# Adapter.net
KiCad netlist of a schematic drawn in Altium Designer
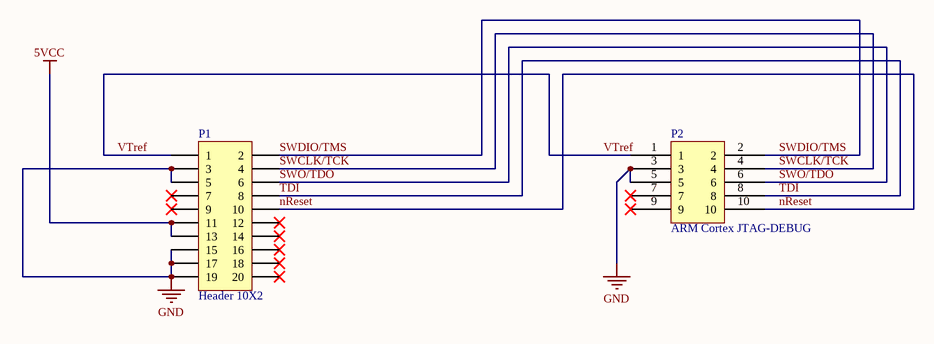
[diagram p0: Adapter.SchDoc]

(export (version "E")
  (design (tool "Eeschema 10.0.6"))
  (components
    (comp (ref "P1")
      (value "Header 10X2")
      (footprint "HDR2X10")
      (description "Header, 10-Pin, Dual row")
      (fields (field (name "PUBLISHER") "Altium Limited"))
      (libsource (lib "Miscellaneous Connectors") (part "Header 10X2"))
    )
    (comp (ref "P2")
      (value "ARM Cortex JTAG-DEBUG")
      (footprint "FTSH-105-XX-X-DV")
      (libsource (lib "Adams Altium Library") (part "ARM Cortex JTAG-DEBUG Header"))
    )
  )
  (nets
    (net (code "1") (name "/SWCLK{slash}TCK") (class "Default")
      (node (ref "P1") (pin "4") (pinfunction "4_4") (pintype "passive"))
      (node (ref "P2") (pin "4") (pinfunction "4_4") (pintype "passive"))
    )
    (net (code "2") (name "/SWDIO{slash}TMS") (class "Default")
      (node (ref "P1") (pin "2") (pinfunction "2_2") (pintype "passive"))
      (node (ref "P2") (pin "2") (pinfunction "2_2") (pintype "passive"))
    )
    (net (code "3") (name "/SWO{slash}TDO") (class "Default")
      (node (ref "P1") (pin "6") (pinfunction "6_6") (pintype "passive"))
      (node (ref "P2") (pin "6") (pinfunction "6_6") (pintype "passive"))
    )
    (net (code "4") (name "/TDI") (class "Default")
      (node (ref "P1") (pin "8") (pinfunction "8_8") (pintype "passive"))
      (node (ref "P2") (pin "8") (pinfunction "8_8") (pintype "passive"))
    )
    (net (code "5") (name "/VTref") (class "Default")
      (node (ref "P1") (pin "1") (pinfunction "1_1") (pintype "passive"))
      (node (ref "P2") (pin "1") (pinfunction "1_1") (pintype "passive"))
    )
    (net (code "6") (name "/nReset") (class "Default")
      (node (ref "P1") (pin "10") (pinfunction "10_10") (pintype "passive"))
      (node (ref "P2") (pin "10") (pinfunction "10_10") (pintype "passive"))
    )
    (net (code "7") (name "5VCC") (class "Default")
      (node (ref "P1") (pin "11") (pinfunction "11_11") (pintype "passive"))
      (node (ref "P1") (pin "13") (pinfunction "13_13") (pintype "passive"))
    )
    (net (code "8") (name "GND") (class "Default")
      (node (ref "P1") (pin "15") (pinfunction "15_15") (pintype "passive"))
      (node (ref "P1") (pin "17") (pinfunction "17_17") (pintype "passive"))
      (node (ref "P1") (pin "19") (pinfunction "19_19") (pintype "passive"))
      (node (ref "P1") (pin "3") (pinfunction "3_3") (pintype "passive"))
      (node (ref "P1") (pin "5") (pinfunction "5_5") (pintype "passive"))
      (node (ref "P2") (pin "3") (pinfunction "3_3") (pintype "passive"))
      (node (ref "P2") (pin "5") (pinfunction "5_5") (pintype "passive"))
    )
    (net (code "9") (name "unconnected-(P1-Pad7)") (class "Default")
      (node (ref "P1") (pin "7") (pinfunction "7_7") (pintype "passive+no_connect"))
    )
    (net (code "10") (name "unconnected-(P1-Pad9)") (class "Default")
      (node (ref "P1") (pin "9") (pinfunction "9_9") (pintype "passive+no_connect"))
    )
    (net (code "11") (name "unconnected-(P1-Pad12)") (class "Default")
      (node (ref "P1") (pin "12") (pinfunction "12_12") (pintype "passive+no_connect"))
    )
    (net (code "12") (name "unconnected-(P1-Pad14)") (class "Default")
      (node (ref "P1") (pin "14") (pinfunction "14_14") (pintype "passive+no_connect"))
    )
    (net (code "13") (name "unconnected-(P1-Pad16)") (class "Default")
      (node (ref "P1") (pin "16") (pinfunction "16_16") (pintype "passive+no_connect"))
    )
    (net (code "14") (name "unconnected-(P1-Pad18)") (class "Default")
      (node (ref "P1") (pin "18") (pinfunction "18_18") (pintype "passive+no_connect"))
    )
    (net (code "15") (name "unconnected-(P1-Pad20)") (class "Default")
      (node (ref "P1") (pin "20") (pinfunction "20_20") (pintype "passive+no_connect"))
    )
    (net (code "16") (name "unconnected-(P2-Pad7)") (class "Default")
      (node (ref "P2") (pin "7") (pinfunction "7_7") (pintype "passive+no_connect"))
    )
    (net (code "17") (name "unconnected-(P2-Pad9)") (class "Default")
      (node (ref "P2") (pin "9") (pinfunction "9_9") (pintype "passive+no_connect"))
    )
  )
)
